# x2-feed.net
KiCad netlist of a schematic drawn in EAGLE
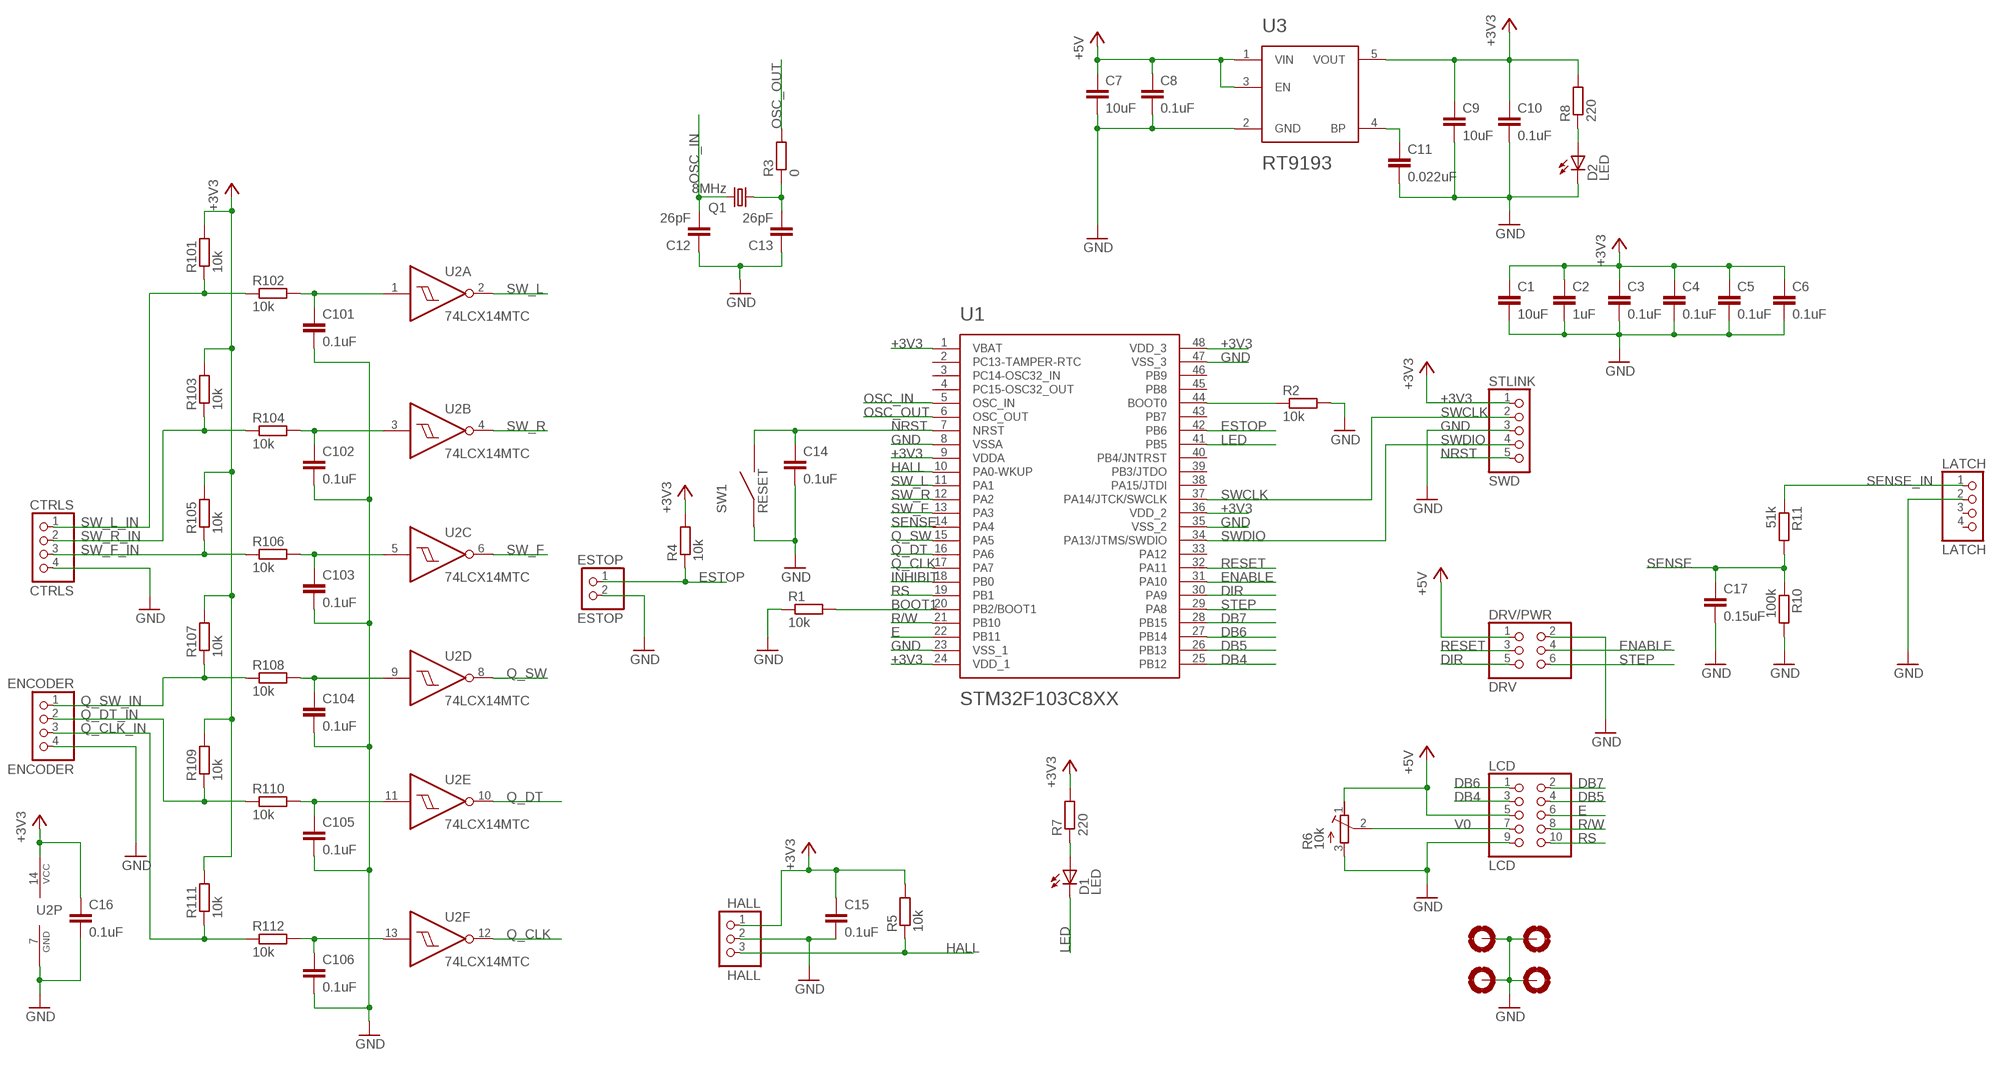
[diagram p0: schematic, sheet 1]

(export (version "E")
  (design (tool "Eeschema 10.0.6"))
  (components
    (comp (ref "C1")
      (value "10uF")
      (footprint "eagle-import:C2012")
      (libsource (lib "eagle-import") (part "CC2012"))
    )
    (comp (ref "C2")
      (value "1uF")
      (footprint "eagle-import:C1608")
      (libsource (lib "eagle-import") (part "CC1608"))
    )
    (comp (ref "C3")
      (value "0.1uF")
      (footprint "eagle-import:C1608")
      (libsource (lib "eagle-import") (part "CC1608"))
    )
    (comp (ref "C4")
      (value "0.1uF")
      (footprint "eagle-import:C1608")
      (libsource (lib "eagle-import") (part "CC1608"))
    )
    (comp (ref "C5")
      (value "0.1uF")
      (footprint "eagle-import:C1608")
      (libsource (lib "eagle-import") (part "CC1608"))
    )
    (comp (ref "C6")
      (value "0.1uF")
      (footprint "eagle-import:C1608")
      (libsource (lib "eagle-import") (part "CC1608"))
    )
    (comp (ref "C7")
      (value "10uF")
      (footprint "eagle-import:C2012")
      (libsource (lib "eagle-import") (part "CC2012"))
    )
    (comp (ref "C8")
      (value "0.1uF")
      (footprint "eagle-import:C1608")
      (libsource (lib "eagle-import") (part "CC1608"))
    )
    (comp (ref "C9")
      (value "10uF")
      (footprint "eagle-import:C2012")
      (libsource (lib "eagle-import") (part "CC2012"))
    )
    (comp (ref "C10")
      (value "0.1uF")
      (footprint "eagle-import:C1608")
      (libsource (lib "eagle-import") (part "CC1608"))
    )
    (comp (ref "C11")
      (value "0.022uF")
      (footprint "eagle-import:C1608")
      (libsource (lib "eagle-import") (part "CC1608"))
    )
    (comp (ref "C12")
      (value "26pF")
      (footprint "eagle-import:C1608")
      (libsource (lib "eagle-import") (part "CC1608"))
    )
    (comp (ref "C13")
      (value "26pF")
      (footprint "eagle-import:C1608")
      (libsource (lib "eagle-import") (part "CC1608"))
    )
    (comp (ref "C14")
      (value "0.1uF")
      (footprint "eagle-import:C1608")
      (libsource (lib "eagle-import") (part "CC1608"))
    )
    (comp (ref "C15")
      (value "0.1uF")
      (footprint "eagle-import:C1608")
      (libsource (lib "eagle-import") (part "CC1608"))
    )
    (comp (ref "C16")
      (value "0.1uF")
      (footprint "eagle-import:C1608")
      (libsource (lib "eagle-import") (part "CC1608"))
    )
    (comp (ref "C17")
      (value "0.15uF")
      (footprint "eagle-import:C1608")
      (libsource (lib "eagle-import") (part "CC1608"))
    )
    (comp (ref "C101")
      (value "0.1uF")
      (footprint "eagle-import:C1608")
      (libsource (lib "eagle-import") (part "CC1608"))
    )
    (comp (ref "C102")
      (value "0.1uF")
      (footprint "eagle-import:C1608")
      (libsource (lib "eagle-import") (part "CC1608"))
    )
    (comp (ref "C103")
      (value "0.1uF")
      (footprint "eagle-import:C1608")
      (libsource (lib "eagle-import") (part "CC1608"))
    )
    (comp (ref "C104")
      (value "0.1uF")
      (footprint "eagle-import:C1608")
      (libsource (lib "eagle-import") (part "CC1608"))
    )
    (comp (ref "C105")
      (value "0.1uF")
      (footprint "eagle-import:C1608")
      (libsource (lib "eagle-import") (part "CC1608"))
    )
    (comp (ref "C106")
      (value "0.1uF")
      (footprint "eagle-import:C1608")
      (libsource (lib "eagle-import") (part "CC1608"))
    )
    (comp (ref "CTRLS")
      (value "CTRLS")
      (footprint "eagle-import:1X04")
      (libsource (lib "eagle-import") (part "PINHD-1X4"))
    )
    (comp (ref "D1")
      (value "LED")
      (footprint "eagle-import:LED2012")
      (libsource (lib "eagle-import") (part "LED"))
    )
    (comp (ref "D2")
      (value "LED")
      (footprint "eagle-import:LED2012")
      (libsource (lib "eagle-import") (part "LED"))
    )
    (comp (ref "DRV/PWR")
      (value "DRV")
      (footprint "eagle-import:2X03")
      (libsource (lib "eagle-import") (part "PINHD-2X3"))
    )
    (comp (ref "ENCODER")
      (value "ENCODER")
      (footprint "eagle-import:1X04")
      (libsource (lib "eagle-import") (part "PINHD-1X4"))
    )
    (comp (ref "ESTOP")
      (value "ESTOP")
      (footprint "eagle-import:1X02")
      (libsource (lib "eagle-import") (part "PINHD-1X2"))
    )
    (comp (ref "H1")
      (value "MOUNT-PAD-ROUND2.8")
      (footprint "eagle-import:2,8-PAD")
      (libsource (lib "eagle-import") (part "MOUNT-PAD-ROUND2.8"))
    )
    (comp (ref "H2")
      (value "MOUNT-PAD-ROUND2.8")
      (footprint "eagle-import:2,8-PAD")
      (libsource (lib "eagle-import") (part "MOUNT-PAD-ROUND2.8"))
    )
    (comp (ref "H3")
      (value "MOUNT-PAD-ROUND2.8")
      (footprint "eagle-import:2,8-PAD")
      (libsource (lib "eagle-import") (part "MOUNT-PAD-ROUND2.8"))
    )
    (comp (ref "H4")
      (value "MOUNT-PAD-ROUND2.8")
      (footprint "eagle-import:2,8-PAD")
      (libsource (lib "eagle-import") (part "MOUNT-PAD-ROUND2.8"))
    )
    (comp (ref "HALL")
      (value "HALL")
      (footprint "eagle-import:5-103361-1")
      (libsource (lib "eagle-import") (part "5-103361-1"))
    )
    (comp (ref "LATCH")
      (value "LATCH")
      (footprint "eagle-import:1X04")
      (libsource (lib "eagle-import") (part "PINHD-1X4"))
    )
    (comp (ref "LCD")
      (value "LCD")
      (footprint "eagle-import:2X05")
      (libsource (lib "eagle-import") (part "PINHD-2X5"))
    )
    (comp (ref "Q1")
      (value "8MHz")
      (footprint "eagle-import:HC49_S")
      (libsource (lib "eagle-import") (part "CRYSTAL9B"))
    )
    (comp (ref "R1")
      (value "10k")
      (footprint "eagle-import:R1608")
      (libsource (lib "eagle-import") (part "RR1608"))
    )
    (comp (ref "R2")
      (value "10k")
      (footprint "eagle-import:R1608")
      (libsource (lib "eagle-import") (part "RR1608"))
    )
    (comp (ref "R3")
      (value "0")
      (footprint "eagle-import:R1608")
      (libsource (lib "eagle-import") (part "RR1608"))
    )
    (comp (ref "R4")
      (value "10k")
      (footprint "eagle-import:R1608")
      (libsource (lib "eagle-import") (part "RR1608"))
    )
    (comp (ref "R5")
      (value "10k")
      (footprint "eagle-import:R1608")
      (libsource (lib "eagle-import") (part "RR1608"))
    )
    (comp (ref "R6")
      (value "10k")
      (footprint "eagle-import:RTRIMT93YA")
      (libsource (lib "eagle-import") (part "R-TRIMMT93YA"))
    )
    (comp (ref "R7")
      (value "220")
      (footprint "eagle-import:R1608")
      (libsource (lib "eagle-import") (part "RR1608"))
    )
    (comp (ref "R8")
      (value "220")
      (footprint "eagle-import:R1608")
      (libsource (lib "eagle-import") (part "RR1608"))
    )
    (comp (ref "R10")
      (value "100k")
      (footprint "eagle-import:R1608")
      (libsource (lib "eagle-import") (part "RR1608"))
    )
    (comp (ref "R11")
      (value "51k")
      (footprint "eagle-import:R1608")
      (libsource (lib "eagle-import") (part "RR1608"))
    )
    (comp (ref "R101")
      (value "10k")
      (footprint "eagle-import:R1608")
      (libsource (lib "eagle-import") (part "RR1608"))
    )
    (comp (ref "R102")
      (value "10k")
      (footprint "eagle-import:R1608")
      (libsource (lib "eagle-import") (part "RR1608"))
    )
    (comp (ref "R103")
      (value "10k")
      (footprint "eagle-import:R1608")
      (libsource (lib "eagle-import") (part "RR1608"))
    )
    (comp (ref "R104")
      (value "10k")
      (footprint "eagle-import:R1608")
      (libsource (lib "eagle-import") (part "RR1608"))
    )
    (comp (ref "R105")
      (value "10k")
      (footprint "eagle-import:R1608")
      (libsource (lib "eagle-import") (part "RR1608"))
    )
    (comp (ref "R106")
      (value "10k")
      (footprint "eagle-import:R1608")
      (libsource (lib "eagle-import") (part "RR1608"))
    )
    (comp (ref "R107")
      (value "10k")
      (footprint "eagle-import:R1608")
      (libsource (lib "eagle-import") (part "RR1608"))
    )
    (comp (ref "R108")
      (value "10k")
      (footprint "eagle-import:R1608")
      (libsource (lib "eagle-import") (part "RR1608"))
    )
    (comp (ref "R109")
      (value "10k")
      (footprint "eagle-import:R1608")
      (libsource (lib "eagle-import") (part "RR1608"))
    )
    (comp (ref "R110")
      (value "10k")
      (footprint "eagle-import:R1608")
      (libsource (lib "eagle-import") (part "RR1608"))
    )
    (comp (ref "R111")
      (value "10k")
      (footprint "eagle-import:R1608")
      (libsource (lib "eagle-import") (part "RR1608"))
    )
    (comp (ref "R112")
      (value "10k")
      (footprint "eagle-import:R1608")
      (libsource (lib "eagle-import") (part "RR1608"))
    )
    (comp (ref "STLINK")
      (value "SWD")
      (footprint "eagle-import:1X05")
      (libsource (lib "eagle-import") (part "PINHD-1X5"))
    )
    (comp (ref "SW1")
      (value "RESET")
      (footprint "eagle-import:PUSH")
      (libsource (lib "eagle-import") (part "PUSH"))
    )
    (comp (ref "U1")
      (value "STM32F103C8XX")
      (footprint "eagle-import:LQFP48-7X7MM")
      (libsource (lib "eagle-import") (part "STM32F103C8XX"))
    )
    (comp (ref "U2")
      (value "74LCX14MTC")
      (footprint "eagle-import:TSSOP14")
      (libsource (lib "eagle-import") (part "74LCX14MTC"))
    )
    (comp (ref "U3")
      (value "RT9193")
      (footprint "eagle-import:SOT23-5L")
      (libsource (lib "eagle-import") (part "RT9193"))
    )
  )
  (nets
    (net (code "1") (name "+3V3") (class "Default")
      (node (ref "C1") (pin "1") (pinfunction "1_1") (pintype "passive"))
      (node (ref "C10") (pin "1") (pinfunction "1_1") (pintype "passive"))
      (node (ref "C15") (pin "1") (pinfunction "1_1") (pintype "passive"))
      (node (ref "C16") (pin "1") (pinfunction "1_1") (pintype "passive"))
      (node (ref "C2") (pin "1") (pinfunction "1_1") (pintype "passive"))
      (node (ref "C3") (pin "1") (pinfunction "1_1") (pintype "passive"))
      (node (ref "C4") (pin "1") (pinfunction "1_1") (pintype "passive"))
      (node (ref "C5") (pin "1") (pinfunction "1_1") (pintype "passive"))
      (node (ref "C6") (pin "1") (pinfunction "1_1") (pintype "passive"))
      (node (ref "C9") (pin "1") (pinfunction "1_1") (pintype "passive"))
      (node (ref "HALL") (pin "1") (pinfunction "1_1") (pintype "passive"))
      (node (ref "R101") (pin "2") (pinfunction "2_2") (pintype "passive"))
      (node (ref "R103") (pin "2") (pinfunction "2_2") (pintype "passive"))
      (node (ref "R105") (pin "2") (pinfunction "2_2") (pintype "passive"))
      (node (ref "R107") (pin "2") (pinfunction "2_2") (pintype "passive"))
      (node (ref "R109") (pin "2") (pinfunction "2_2") (pintype "passive"))
      (node (ref "R111") (pin "2") (pinfunction "2_2") (pintype "passive"))
      (node (ref "R4") (pin "2") (pinfunction "2_2") (pintype "passive"))
      (node (ref "R5") (pin "2") (pinfunction "2_2") (pintype "passive"))
      (node (ref "R7") (pin "2") (pinfunction "2_2") (pintype "passive"))
      (node (ref "R8") (pin "2") (pinfunction "2_2") (pintype "passive"))
      (node (ref "STLINK") (pin "1") (pinfunction "1_1") (pintype "passive"))
      (node (ref "U1") (pin "1") (pinfunction "VBAT_1") (pintype "bidirectional"))
      (node (ref "U1") (pin "24") (pinfunction "VDD_1_24") (pintype "bidirectional"))
      (node (ref "U1") (pin "36") (pinfunction "VDD_2_36") (pintype "bidirectional"))
      (node (ref "U1") (pin "48") (pinfunction "VDD_3_48") (pintype "bidirectional"))
      (node (ref "U1") (pin "9") (pinfunction "VDDA_9") (pintype "bidirectional"))
      (node (ref "U2") (pin "14") (pinfunction "VCC_14") (pintype "power_in"))
      (node (ref "U3") (pin "5") (pinfunction "VOUT_5") (pintype "power_in"))
    )
    (net (code "2") (name "+5V") (class "Default")
      (node (ref "C7") (pin "1") (pinfunction "1_1") (pintype "passive"))
      (node (ref "C8") (pin "1") (pinfunction "1_1") (pintype "passive"))
      (node (ref "DRV/PWR") (pin "1") (pinfunction "1_1") (pintype "passive"))
      (node (ref "LCD") (pin "5") (pinfunction "5_5") (pintype "passive"))
      (node (ref "R6") (pin "1") (pinfunction "E_1") (pintype "passive"))
      (node (ref "U3") (pin "1") (pinfunction "VIN_1") (pintype "power_in"))
      (node (ref "U3") (pin "3") (pinfunction "EN_3") (pintype "bidirectional"))
    )
    (net (code "3") (name "/BOOT1") (class "Default")
      (node (ref "R1") (pin "2") (pinfunction "2_2") (pintype "passive"))
      (node (ref "U1") (pin "20") (pinfunction "PB2/BOOT1_20") (pintype "bidirectional"))
    )
    (net (code "4") (name "/DB4") (class "Default")
      (node (ref "LCD") (pin "3") (pinfunction "3_3") (pintype "passive"))
      (node (ref "U1") (pin "25") (pinfunction "PB12_25") (pintype "bidirectional"))
    )
    (net (code "5") (name "/DB5") (class "Default")
      (node (ref "LCD") (pin "4") (pinfunction "4_4") (pintype "passive"))
      (node (ref "U1") (pin "26") (pinfunction "PB13_26") (pintype "bidirectional"))
    )
    (net (code "6") (name "/DB6") (class "Default")
      (node (ref "LCD") (pin "1") (pinfunction "1_1") (pintype "passive"))
      (node (ref "U1") (pin "27") (pinfunction "PB14_27") (pintype "bidirectional"))
    )
    (net (code "7") (name "/DB7") (class "Default")
      (node (ref "LCD") (pin "2") (pinfunction "2_2") (pintype "passive"))
      (node (ref "U1") (pin "28") (pinfunction "PB15_28") (pintype "bidirectional"))
    )
    (net (code "8") (name "/DIR") (class "Default")
      (node (ref "DRV/PWR") (pin "5") (pinfunction "5_5") (pintype "passive"))
      (node (ref "U1") (pin "30") (pinfunction "PA9_30") (pintype "bidirectional"))
    )
    (net (code "9") (name "/E") (class "Default")
      (node (ref "LCD") (pin "6") (pinfunction "6_6") (pintype "passive"))
      (node (ref "U1") (pin "22") (pinfunction "PB11_22") (pintype "bidirectional"))
    )
    (net (code "10") (name "/ENABLE") (class "Default")
      (node (ref "DRV/PWR") (pin "4") (pinfunction "4_4") (pintype "passive"))
      (node (ref "U1") (pin "31") (pinfunction "PA10_31") (pintype "bidirectional"))
    )
    (net (code "11") (name "/ESTOP") (class "Default")
      (node (ref "ESTOP") (pin "1") (pinfunction "1_1") (pintype "passive"))
      (node (ref "R4") (pin "1") (pinfunction "1_1") (pintype "passive"))
      (node (ref "U1") (pin "42") (pinfunction "PB6_42") (pintype "bidirectional"))
    )
    (net (code "12") (name "/HALL") (class "Default")
      (node (ref "HALL") (pin "3") (pinfunction "3_3") (pintype "passive"))
      (node (ref "R5") (pin "1") (pinfunction "1_1") (pintype "passive"))
      (node (ref "U1") (pin "10") (pinfunction "PA0-WKUP_10") (pintype "bidirectional"))
    )
    (net (code "13") (name "/INHIBIT") (class "Default")
      (node (ref "U1") (pin "18") (pinfunction "PB0_18") (pintype "bidirectional"))
    )
    (net (code "14") (name "/LED") (class "Default")
      (node (ref "D1") (pin "C") (pinfunction "C_C") (pintype "passive"))
      (node (ref "U1") (pin "41") (pinfunction "PB5_41") (pintype "bidirectional"))
    )
    (net (code "15") (name "/NRST") (class "Default")
      (node (ref "C14") (pin "1") (pinfunction "1_1") (pintype "passive"))
      (node (ref "STLINK") (pin "5") (pinfunction "5_5") (pintype "passive"))
      (node (ref "SW1") (pin "3") (pinfunction "2_3") (pintype "bidirectional"))
      (node (ref "SW1") (pin "4") (pinfunction "2_4") (pintype "bidirectional"))
      (node (ref "U1") (pin "7") (pinfunction "NRST_7") (pintype "bidirectional"))
    )
    (net (code "16") (name "/OSC_IN") (class "Default")
      (node (ref "C12") (pin "2") (pinfunction "2_2") (pintype "passive"))
      (node (ref "Q1") (pin "2") (pinfunction "2_2") (pintype "passive"))
      (node (ref "U1") (pin "5") (pinfunction "OSC_IN_5") (pintype "bidirectional"))
    )
    (net (code "17") (name "/OSC_OUT") (class "Default")
      (node (ref "R3") (pin "2") (pinfunction "2_2") (pintype "passive"))
      (node (ref "U1") (pin "6") (pinfunction "OSC_OUT_6") (pintype "bidirectional"))
    )
    (net (code "18") (name "/Q_CLK") (class "Default")
      (node (ref "U1") (pin "17") (pinfunction "PA7_17") (pintype "bidirectional"))
      (node (ref "U2") (pin "12") (pinfunction "O_12") (pintype "output"))
    )
    (net (code "19") (name "/Q_CLK_IN") (class "Default")
      (node (ref "ENCODER") (pin "3") (pinfunction "3_3") (pintype "passive"))
      (node (ref "R111") (pin "1") (pinfunction "1_1") (pintype "passive"))
      (node (ref "R112") (pin "1") (pinfunction "1_1") (pintype "passive"))
    )
    (net (code "20") (name "/Q_DT") (class "Default")
      (node (ref "U1") (pin "16") (pinfunction "PA6_16") (pintype "bidirectional"))
      (node (ref "U2") (pin "10") (pinfunction "O_10") (pintype "output"))
    )
    (net (code "21") (name "/Q_DT_IN") (class "Default")
      (node (ref "ENCODER") (pin "2") (pinfunction "2_2") (pintype "passive"))
      (node (ref "R109") (pin "1") (pinfunction "1_1") (pintype "passive"))
      (node (ref "R110") (pin "1") (pinfunction "1_1") (pintype "passive"))
    )
    (net (code "22") (name "/Q_SW") (class "Default")
      (node (ref "U1") (pin "15") (pinfunction "PA5_15") (pintype "bidirectional"))
      (node (ref "U2") (pin "8") (pinfunction "O_8") (pintype "output"))
    )
    (net (code "23") (name "/Q_SW_IN") (class "Default")
      (node (ref "ENCODER") (pin "1") (pinfunction "1_1") (pintype "passive"))
      (node (ref "R107") (pin "1") (pinfunction "1_1") (pintype "passive"))
      (node (ref "R108") (pin "1") (pinfunction "1_1") (pintype "passive"))
    )
    (net (code "24") (name "/RESET") (class "Default")
      (node (ref "DRV/PWR") (pin "3") (pinfunction "3_3") (pintype "passive"))
      (node (ref "U1") (pin "32") (pinfunction "PA11_32") (pintype "bidirectional"))
    )
    (net (code "25") (name "/RS") (class "Default")
      (node (ref "LCD") (pin "10") (pinfunction "10_10") (pintype "passive"))
      (node (ref "U1") (pin "19") (pinfunction "PB1_19") (pintype "bidirectional"))
    )
    (net (code "26") (name "/R{slash}W") (class "Default")
      (node (ref "LCD") (pin "8") (pinfunction "8_8") (pintype "passive"))
      (node (ref "U1") (pin "21") (pinfunction "PB10_21") (pintype "bidirectional"))
    )
    (net (code "27") (name "/SENSE") (class "Default")
      (node (ref "C17") (pin "1") (pinfunction "1_1") (pintype "passive"))
      (node (ref "R10") (pin "1") (pinfunction "1_1") (pintype "passive"))
      (node (ref "R11") (pin "2") (pinfunction "2_2") (pintype "passive"))
      (node (ref "U1") (pin "14") (pinfunction "PA4_14") (pintype "bidirectional"))
    )
    (net (code "28") (name "/SENSE_IN") (class "Default")
      (node (ref "LATCH") (pin "1") (pinfunction "1_1") (pintype "passive"))
      (node (ref "R11") (pin "1") (pinfunction "1_1") (pintype "passive"))
    )
    (net (code "29") (name "/STEP") (class "Default")
      (node (ref "DRV/PWR") (pin "6") (pinfunction "6_6") (pintype "passive"))
      (node (ref "U1") (pin "29") (pinfunction "PA8_29") (pintype "bidirectional"))
    )
    (net (code "30") (name "/SWCLK") (class "Default")
      (node (ref "STLINK") (pin "2") (pinfunction "2_2") (pintype "passive"))
      (node (ref "U1") (pin "37") (pinfunction "PA14/JTCK/SWCLK_37") (pintype "bidirectional"))
    )
    (net (code "31") (name "/SWDIO") (class "Default")
      (node (ref "STLINK") (pin "4") (pinfunction "4_4") (pintype "passive"))
      (node (ref "U1") (pin "34") (pinfunction "PA13/JTMS/SWDIO_34") (pintype "bidirectional"))
    )
    (net (code "32") (name "/SW_F") (class "Default")
      (node (ref "U1") (pin "13") (pinfunction "PA3_13") (pintype "bidirectional"))
      (node (ref "U2") (pin "6") (pinfunction "O_6") (pintype "output"))
    )
    (net (code "33") (name "/SW_F_IN") (class "Default")
      (node (ref "CTRLS") (pin "3") (pinfunction "3_3") (pintype "passive"))
      (node (ref "R105") (pin "1") (pinfunction "1_1") (pintype "passive"))
      (node (ref "R106") (pin "1") (pinfunction "1_1") (pintype "passive"))
    )
    (net (code "34") (name "/SW_L") (class "Default")
      (node (ref "U1") (pin "11") (pinfunction "PA1_11") (pintype "bidirectional"))
      (node (ref "U2") (pin "2") (pinfunction "O_2") (pintype "output"))
    )
    (net (code "35") (name "/SW_L_IN") (class "Default")
      (node (ref "CTRLS") (pin "1") (pinfunction "1_1") (pintype "passive"))
      (node (ref "R101") (pin "1") (pinfunction "1_1") (pintype "passive"))
      (node (ref "R102") (pin "1") (pinfunction "1_1") (pintype "passive"))
    )
    (net (code "36") (name "/SW_R") (class "Default")
      (node (ref "U1") (pin "12") (pinfunction "PA2_12") (pintype "bidirectional"))
      (node (ref "U2") (pin "4") (pinfunction "O_4") (pintype "output"))
    )
    (net (code "37") (name "/SW_R_IN") (class "Default")
      (node (ref "CTRLS") (pin "2") (pinfunction "2_2") (pintype "passive"))
      (node (ref "R103") (pin "1") (pinfunction "1_1") (pintype "passive"))
      (node (ref "R104") (pin "1") (pinfunction "1_1") (pintype "passive"))
    )
    (net (code "38") (name "/V0") (class "Default")
      (node (ref "LCD") (pin "7") (pinfunction "7_7") (pintype "passive"))
      (node (ref "R6") (pin "2") (pinfunction "S_2") (pintype "passive"))
    )
    (net (code "39") (name "GND") (class "Default")
      (node (ref "C1") (pin "2") (pinfunction "2_2") (pintype "passive"))
      (node (ref "C10") (pin "2") (pinfunction "2_2") (pintype "passive"))
      (node (ref "C101") (pin "2") (pinfunction "2_2") (pintype "passive"))
      (node (ref "C102") (pin "2") (pinfunction "2_2") (pintype "passive"))
      (node (ref "C103") (pin "2") (pinfunction "2_2") (pintype "passive"))
      (node (ref "C104") (pin "2") (pinfunction "2_2") (pintype "passive"))
      (node (ref "C105") (pin "2") (pinfunction "2_2") (pintype "passive"))
      (node (ref "C106") (pin "2") (pinfunction "2_2") (pintype "passive"))
      (node (ref "C11") (pin "2") (pinfunction "2_2") (pintype "passive"))
      (node (ref "C12") (pin "1") (pinfunction "1_1") (pintype "passive"))
      (node (ref "C13") (pin "1") (pinfunction "1_1") (pintype "passive"))
      (node (ref "C14") (pin "2") (pinfunction "2_2") (pintype "passive"))
      (node (ref "C15") (pin "2") (pinfunction "2_2") (pintype "passive"))
      (node (ref "C16") (pin "2") (pinfunction "2_2") (pintype "passive"))
      (node (ref "C17") (pin "2") (pinfunction "2_2") (pintype "passive"))
      (node (ref "C2") (pin "2") (pinfunction "2_2") (pintype "passive"))
      (node (ref "C3") (pin "2") (pinfunction "2_2") (pintype "passive"))
      (node (ref "C4") (pin "2") (pinfunction "2_2") (pintype "passive"))
      (node (ref "C5") (pin "2") (pinfunction "2_2") (pintype "passive"))
      (node (ref "C6") (pin "2") (pinfunction "2_2") (pintype "passive"))
      (node (ref "C7") (pin "2") (pinfunction "2_2") (pintype "passive"))
      (node (ref "C8") (pin "2") (pinfunction "2_2") (pintype "passive"))
      (node (ref "C9") (pin "2") (pinfunction "2_2") (pintype "passive"))
      (node (ref "CTRLS") (pin "4") (pinfunction "4_4") (pintype "passive"))
      (node (ref "D2") (pin "C") (pinfunction "C_C") (pintype "passive"))
      (node (ref "DRV/PWR") (pin "2") (pinfunction "2_2") (pintype "passive"))
      (node (ref "ENCODER") (pin "4") (pinfunction "4_4") (pintype "passive"))
      (node (ref "ESTOP") (pin "2") (pinfunction "2_2") (pintype "passive"))
      (node (ref "H1") (pin "B2,8") (pinfunction "MOUNT_B2,8") (pintype "passive"))
      (node (ref "H2") (pin "B2,8") (pinfunction "MOUNT_B2,8") (pintype "passive"))
      (node (ref "H3") (pin "B2,8") (pinfunction "MOUNT_B2,8") (pintype "passive"))
      (node (ref "H4") (pin "B2,8") (pinfunction "MOUNT_B2,8") (pintype "passive"))
      (node (ref "HALL") (pin "2") (pinfunction "2_2") (pintype "passive"))
      (node (ref "LATCH") (pin "2") (pinfunction "2_2") (pintype "passive"))
      (node (ref "LCD") (pin "9") (pinfunction "9_9") (pintype "passive"))
      (node (ref "R1") (pin "1") (pinfunction "1_1") (pintype "passive"))
      (node (ref "R10") (pin "2") (pinfunction "2_2") (pintype "passive"))
      (node (ref "R2") (pin "2") (pinfunction "2_2") (pintype "passive"))
      (node (ref "R6") (pin "3") (pinfunction "A_3") (pintype "passive"))
      (node (ref "STLINK") (pin "3") (pinfunction "3_3") (pintype "passive"))
      (node (ref "SW1") (pin "1") (pinfunction "1_1") (pintype "bidirectional"))
      (node (ref "SW1") (pin "2") (pinfunction "1_2") (pintype "bidirectional"))
      (node (ref "U1") (pin "23") (pinfunction "VSS_1_23") (pintype "bidirectional"))
      (node (ref "U1") (pin "35") (pinfunction "VSS_2_35") (pintype "bidirectional"))
      (node (ref "U1") (pin "47") (pinfunction "VSS_3_47") (pintype "bidirectional"))
      (node (ref "U1") (pin "8") (pinfunction "VSSA_8") (pintype "bidirectional"))
      (node (ref "U2") (pin "7") (pinfunction "GND_7") (pintype "power_in"))
      (node (ref "U3") (pin "2") (pinfunction "GND_2") (pintype "power_in"))
    )
    (net (code "40") (name "Net-(C13-Pad2)") (class "Default")
      (node (ref "C13") (pin "2") (pinfunction "2_2") (pintype "passive"))
      (node (ref "Q1") (pin "1") (pinfunction "1_1") (pintype "passive"))
      (node (ref "R3") (pin "1") (pinfunction "1_1") (pintype "passive"))
    )
    (net (code "41") (name "Net-(D1-PadA)") (class "Default")
      (node (ref "D1") (pin "A") (pinfunction "A_A") (pintype "passive"))
      (node (ref "R7") (pin "1") (pinfunction "1_1") (pintype "passive"))
    )
    (net (code "42") (name "Net-(D2-PadA)") (class "Default")
      (node (ref "D2") (pin "A") (pinfunction "A_A") (pintype "passive"))
      (node (ref "R8") (pin "1") (pinfunction "1_1") (pintype "passive"))
    )
    (net (code "43") (name "Net-(U1-BOOT0)") (class "Default")
      (node (ref "R2") (pin "1") (pinfunction "1_1") (pintype "passive"))
      (node (ref "U1") (pin "44") (pinfunction "BOOT0_44") (pintype "bidirectional"))
    )
    (net (code "44") (name "Net-(U2A-I)") (class "Default")
      (node (ref "C101") (pin "1") (pinfunction "1_1") (pintype "passive"))
      (node (ref "R102") (pin "2") (pinfunction "2_2") (pintype "passive"))
      (node (ref "U2") (pin "1") (pinfunction "I_1") (pintype "input"))
    )
    (net (code "45") (name "Net-(U2B-I)") (class "Default")
      (node (ref "C102") (pin "1") (pinfunction "1_1") (pintype "passive"))
      (node (ref "R104") (pin "2") (pinfunction "2_2") (pintype "passive"))
      (node (ref "U2") (pin "3") (pinfunction "I_3") (pintype "input"))
    )
    (net (code "46") (name "Net-(U2C-I)") (class "Default")
      (node (ref "C103") (pin "1") (pinfunction "1_1") (pintype "passive"))
      (node (ref "R106") (pin "2") (pinfunction "2_2") (pintype "passive"))
      (node (ref "U2") (pin "5") (pinfunction "I_5") (pintype "input"))
    )
    (net (code "47") (name "Net-(U2D-I)") (class "Default")
      (node (ref "C104") (pin "1") (pinfunction "1_1") (pintype "passive"))
      (node (ref "R108") (pin "2") (pinfunction "2_2") (pintype "passive"))
      (node (ref "U2") (pin "9") (pinfunction "I_9") (pintype "input"))
    )
    (net (code "48") (name "Net-(U2E-I)") (class "Default")
      (node (ref "C105") (pin "1") (pinfunction "1_1") (pintype "passive"))
      (node (ref "R110") (pin "2") (pinfunction "2_2") (pintype "passive"))
      (node (ref "U2") (pin "11") (pinfunction "I_11") (pintype "input"))
    )
    (net (code "49") (name "Net-(U2F-I)") (class "Default")
      (node (ref "C106") (pin "1") (pinfunction "1_1") (pintype "passive"))
      (node (ref "R112") (pin "2") (pinfunction "2_2") (pintype "passive"))
      (node (ref "U2") (pin "13") (pinfunction "I_13") (pintype "input"))
    )
    (net (code "50") (name "Net-(U3-BP)") (class "Default")
      (node (ref "C11") (pin "1") (pinfunction "1_1") (pintype "passive"))
      (node (ref "U3") (pin "4") (pinfunction "BP_4") (pintype "bidirectional"))
    )
    (net (code "51") (name "unconnected-(LATCH-Pad3)") (class "Default")
      (node (ref "LATCH") (pin "3") (pinfunction "3_3") (pintype "passive"))
    )
    (net (code "52") (name "unconnected-(LATCH-Pad4)") (class "Default")
      (node (ref "LATCH") (pin "4") (pinfunction "4_4") (pintype "passive"))
    )
    (net (code "53") (name "unconnected-(U1-PA12-Pad33)") (class "Default")
      (node (ref "U1") (pin "33") (pinfunction "PA12_33") (pintype "bidirectional"))
    )
    (net (code "54") (name "unconnected-(U1-PA15{slash}JTDI-Pad38)") (class "Default")
      (node (ref "U1") (pin "38") (pinfunction "PA15/JTDI_38") (pintype "bidirectional"))
    )
    (net (code "55") (name "unconnected-(U1-PB3{slash}JTDO-Pad39)") (class "Default")
      (node (ref "U1") (pin "39") (pinfunction "PB3/JTDO_39") (pintype "bidirectional"))
    )
    (net (code "56") (name "unconnected-(U1-PB4{slash}JNTRST-Pad40)") (class "Default")
      (node (ref "U1") (pin "40") (pinfunction "PB4/JNTRST_40") (pintype "bidirectional"))
    )
    (net (code "57") (name "unconnected-(U1-PB7-Pad43)") (class "Default")
      (node (ref "U1") (pin "43") (pinfunction "PB7_43") (pintype "bidirectional"))
    )
    (net (code "58") (name "unconnected-(U1-PB8-Pad45)") (class "Default")
      (node (ref "U1") (pin "45") (pinfunction "PB8_45") (pintype "bidirectional"))
    )
    (net (code "59") (name "unconnected-(U1-PB9-Pad46)") (class "Default")
      (node (ref "U1") (pin "46") (pinfunction "PB9_46") (pintype "bidirectional"))
    )
    (net (code "60") (name "unconnected-(U1-PC13-TAMPER-RTC-Pad2)") (class "Default")
      (node (ref "U1") (pin "2") (pinfunction "PC13-TAMPER-RTC_2") (pintype "bidirectional"))
    )
    (net (code "61") (name "unconnected-(U1-PC14-OSC32_IN-Pad3)") (class "Default")
      (node (ref "U1") (pin "3") (pinfunction "PC14-OSC32_IN_3") (pintype "bidirectional"))
    )
    (net (code "62") (name "unconnected-(U1-PC15-OSC32_OUT-Pad4)") (class "Default")
      (node (ref "U1") (pin "4") (pinfunction "PC15-OSC32_OUT_4") (pintype "bidirectional"))
    )
  )
)
